# 15_Power_DCIN.net
KiCad netlist of a schematic drawn in Altium Designer
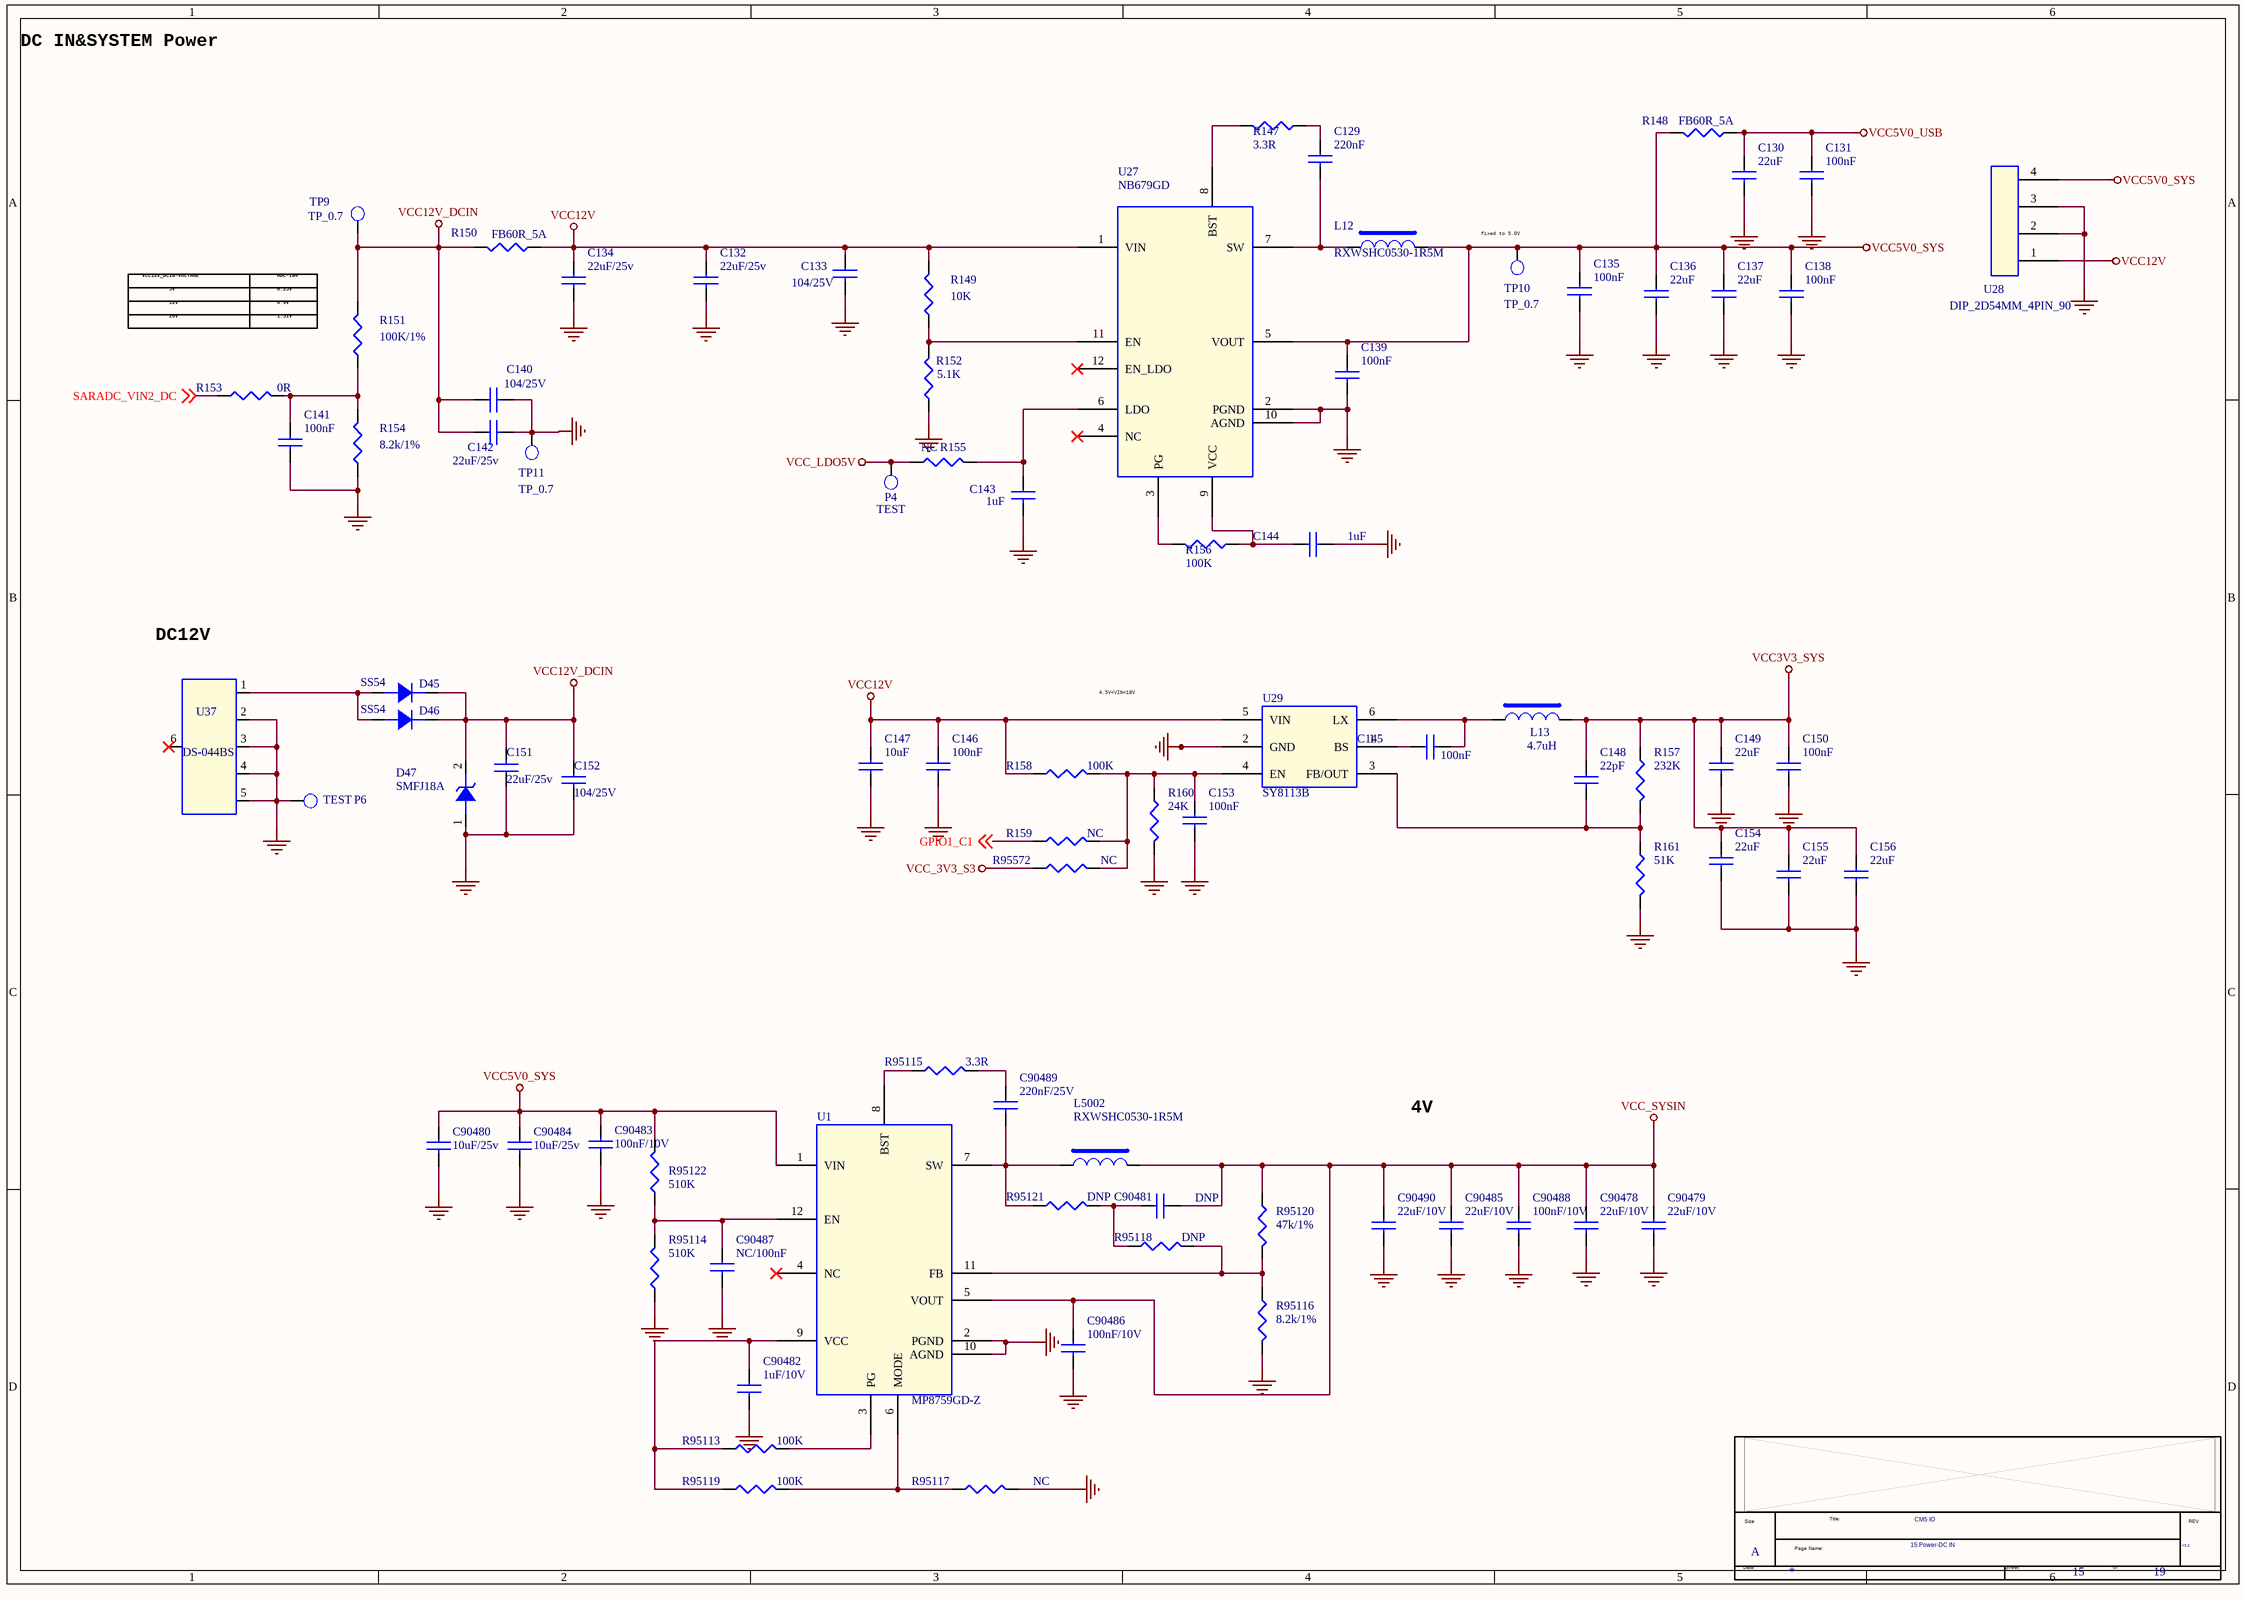
[diagram p0: 15_Power_DCIN.SchDoc]

(export (version "E")
  (design (tool "Eeschema 10.0.6"))
  (components
    (comp (ref "*")
      (value "radxa_1010")
      (fields
        (field (name "DOC") "15.Power-DC IN")
        (field (name "REVCODE") "V2.2")
        (field (name "TITLE") "CM5 IO")
        (field (name "PAGE SIZE") "A")
        (field (name "PAGE NUMBER") "15")
        (field (name "PAGE COUNT") "19")
      )
      (libsource (lib "*") (part "radxa_1010"))
    )
    (comp (ref "C129")
      (value "220nF")
      (footprint "C0402")
      (description "cap,220.00nF,+/-10%,25V,X5R,C0402")
      (fields
        (field (name "VOLTAGE") "25V")
        (field (name "MANUFACTURER") "TDK")
        (field (name "CREATED BY") "JJJ")
      )
      (libsource (lib "*") (part "CAP NP_0"))
    )
    (comp (ref "C130")
      (value "22uF")
      (footprint "C0603")
      (description "cap,22.00uF,+/-10%,10V,X5R,C0805")
      (fields
        (field (name "VOLTAGE") "10V")
        (field (name "TOLERANCE") "10%")
        (field (name "CREATED BY") "JJJ")
      )
      (libsource (lib "*") (part "CAP NP_0"))
    )
    (comp (ref "C131")
      (value "100nF")
      (footprint "C0402")
      (description "cap,100.00nF,+/-10%,16V,X5R,C0402")
      (fields
        (field (name "VOLTAGE") "16V")
        (field (name "MANUFACTURER") "TDK")
        (field (name "CREATED BY") "JJJ")
      )
      (libsource (lib "*") (part "CAP NP_0"))
    )
    (comp (ref "C132")
      (value "22uF/25v")
      (footprint "C0805")
      (description "cap,10.00uF,+/-10%,16V,X5R,C0805")
      (fields
        (field (name "VOLTAGE") "16V")
        (field (name "TOLERANCE") "10%")
        (field (name "CREATED BY") "JJJ")
      )
      (libsource (lib "*") (part "CAP NP_0"))
    )
    (comp (ref "C133")
      (value "104/25V")
      (footprint "C0402")
      (description "cap,1.00uF,+/-10%,16V,X5R,C0402")
      (fields
        (field (name "VOLTAGE") "25V")
        (field (name "MANUFACTURER") "TDK")
        (field (name "CREATED BY") "JJJ")
      )
      (libsource (lib "*") (part "CAP NP_0"))
    )
    (comp (ref "C134")
      (value "22uF/25v")
      (footprint "C0805")
      (description "cap,10.00uF,+/-10%,16V,X5R,C0805")
      (fields
        (field (name "VOLTAGE") "16V")
        (field (name "MANUFACTURER") "TDK")
        (field (name "CREATED BY") "JJJ")
      )
      (libsource (lib "*") (part "CAP NP_0"))
    )
    (comp (ref "C135")
      (value "100nF")
      (footprint "C0402")
      (description "cap,100.00nF,+/-10%,16V,X5R,C0402")
      (fields
        (field (name "VOLTAGE") "16V")
        (field (name "MANUFACTURER") "TDK")
        (field (name "CREATED BY") "JJJ")
      )
      (libsource (lib "*") (part "CAP NP_0"))
    )
    (comp (ref "C136")
      (value "22uF")
      (footprint "C0603")
      (description "cap,22.00uF,+/-10%,10V,X5R,C0805")
      (fields
        (field (name "VOLTAGE") "10V")
        (field (name "TOLERANCE") "10%")
        (field (name "CREATED BY") "JJJ")
      )
      (libsource (lib "*") (part "CAP NP_0"))
    )
    (comp (ref "C137")
      (value "22uF")
      (footprint "C0603")
      (description "cap,22.00uF,+/-10%,10V,X5R,C0805")
      (fields
        (field (name "VOLTAGE") "10V")
        (field (name "TOLERANCE") "10%")
        (field (name "CREATED BY") "JJJ")
      )
      (libsource (lib "*") (part "CAP NP_0"))
    )
    (comp (ref "C138")
      (value "100nF")
      (footprint "C0402")
      (description "cap,100.00nF,+/-10%,16V,X5R,C0402")
      (fields
        (field (name "VOLTAGE") "16V")
        (field (name "MANUFACTURER") "TDK")
        (field (name "CREATED BY") "JJJ")
      )
      (libsource (lib "*") (part "CAP NP_0"))
    )
    (comp (ref "C139")
      (value "100nF")
      (footprint "C0402")
      (description "cap,100.00nF,+/-10%,16V,X5R,C0402")
      (fields
        (field (name "VOLTAGE") "16V")
        (field (name "MANUFACTURER") "TDK")
        (field (name "CREATED BY") "JJJ")
      )
      (libsource (lib "*") (part "CAP NP_0"))
    )
    (comp (ref "C140")
      (value "104/25V")
      (footprint "C0402")
      (description "cap,1.00uF,+/-10%,16V,X5R,C0402")
      (fields
        (field (name "VOLTAGE") "25V")
        (field (name "MANUFACTURER") "TDK")
        (field (name "CREATED BY") "JJJ")
      )
      (libsource (lib "*") (part "CAP NP_0"))
    )
    (comp (ref "C141")
      (value "100nF")
      (footprint "C0402")
      (description "cap,100.00nF,+/-10%,16V,X5R,C0402")
      (fields
        (field (name "VOLTAGE") "16V")
        (field (name "TOLERANCE") "10%")
        (field (name "CREATED BY") "JJJ")
      )
      (libsource (lib "*") (part "CAP NP_0"))
    )
    (comp (ref "C142")
      (value "22uF/25v")
      (footprint "C0805")
      (description "cap,10.00uF,+/-10%,16V,X5R,C0805")
      (fields
        (field (name "VOLTAGE") "16V")
        (field (name "TOLERANCE") "10%")
        (field (name "CREATED BY") "JJJ")
      )
      (libsource (lib "*") (part "CAP NP_0"))
    )
    (comp (ref "C143")
      (value "1uF")
      (footprint "C0402")
      (description "cap,1.00uF,+/-10%,16V,X5R,C0402")
      (fields
        (field (name "VOLTAGE") "16V")
        (field (name "TOLERANCE") "10%")
        (field (name "CREATED BY") "JJJ")
      )
      (libsource (lib "*") (part "CAP NP_0"))
    )
    (comp (ref "C144")
      (value "1uF")
      (footprint "C0402")
      (description "cap,1.00uF,+/-10%,16V,X5R,C0402")
      (fields
        (field (name "VOLTAGE") "16V")
        (field (name "MANUFACTURER") "TDK")
        (field (name "CREATED BY") "JJJ")
      )
      (libsource (lib "*") (part "CAP NP_0"))
    )
    (comp (ref "C145")
      (value "100nF")
      (footprint "C0402")
      (description "cap,100.00nF,+/-10%,25V,X5R,C0402")
      (fields
        (field (name "VOLTAGE") "25V")
        (field (name "TOLERANCE") "10%")
        (field (name "CREATED BY") "JJJ")
      )
      (libsource (lib "*") (part "CAP NP_0"))
    )
    (comp (ref "C146")
      (value "100nF")
      (footprint "C0402")
      (description "cap,100.00nF,+/-10%,25V,X5R,C0402")
      (fields
        (field (name "VOLTAGE") "25V")
        (field (name "TOLERANCE") "10%")
        (field (name "CREATED BY") "JJJ")
      )
      (libsource (lib "*") (part "CAP NP_0"))
    )
    (comp (ref "C147")
      (value "10uF")
      (footprint "C1206")
      (description "cap,10.00uF,+/-10%,25V,X5R,C1206")
      (fields
        (field (name "VOLTAGE") "25V")
        (field (name "TOLERANCE") "10%")
        (field (name "CREATED BY") "JJJ")
      )
      (libsource (lib "*") (part "CAP NP_0"))
    )
    (comp (ref "C148")
      (value "22pF")
      (footprint "C0402")
      (description "cap,22.00pF,+/-5%,50V,C0G,C0402")
      (fields
        (field (name "VOLTAGE") "50V")
        (field (name "MANUFACTURER") "TDK")
        (field (name "CREATED BY") "JJJ")
      )
      (libsource (lib "*") (part "CAP NP_0"))
    )
    (comp (ref "C149")
      (value "22uF")
      (footprint "C0805")
      (description "cap,22.00uF,+/-10%,10V,X5R,C0805")
      (fields
        (field (name "VOLTAGE") "10V")
        (field (name "TOLERANCE") "10%")
        (field (name "CREATED BY") "JJJ")
      )
      (libsource (lib "*") (part "CAP NP_0"))
    )
    (comp (ref "C150")
      (value "100nF")
      (footprint "C0402")
      (description "cap,100.00nF,+/-10%,10V,X5R,C0402")
      (fields
        (field (name "VOLTAGE") "10V")
        (field (name "TOLERANCE") "10%")
        (field (name "CREATED BY") "JJJ")
      )
      (libsource (lib "*") (part "CAP NP_0"))
    )
    (comp (ref "C151") (value "22uF/25v") (footprint "C0805") (libsource (lib "*") (part "CAP NP_4")))
    (comp (ref "C152")
      (value "104/25V")
      (footprint "C0402")
      (description "CAP,MLCC,1nF,+/-10%,X5R,6.3V,SMD0402")
      (libsource (lib "*") (part "CAP NP"))
    )
    (comp (ref "C153")
      (value "100nF")
      (footprint "C0402")
      (description "cap,100.00nF,+/-10%,10V,X5R,C0402")
      (fields
        (field (name "VOLTAGE") "10V")
        (field (name "MANUFACTURER") "TDK")
        (field (name "CREATED BY") "JJJ")
      )
      (libsource (lib "*") (part "CAP NP_0"))
    )
    (comp (ref "C154")
      (value "22uF")
      (footprint "C0805")
      (description "cap,22.00uF,+/-10%,10V,X5R,C0805")
      (fields
        (field (name "VOLTAGE") "10V")
        (field (name "MANUFACTURER") "TDK")
        (field (name "CREATED BY") "JJJ")
      )
      (libsource (lib "*") (part "CAP NP_0"))
    )
    (comp (ref "C155")
      (value "22uF")
      (footprint "C0805")
      (description "cap,22.00uF,+/-10%,10V,X5R,C0805")
      (fields
        (field (name "VOLTAGE") "10V")
        (field (name "TOLERANCE") "10%")
        (field (name "CREATED BY") "JJJ")
      )
      (libsource (lib "*") (part "CAP NP_0"))
    )
    (comp (ref "C156")
      (value "22uF")
      (footprint "C0805")
      (description "cap,22.00uF,+/-10%,10V,X5R,C0805")
      (fields
        (field (name "VOLTAGE") "10V")
        (field (name "MANUFACTURER") "TDK")
        (field (name "CREATED BY") "JJJ")
      )
      (libsource (lib "*") (part "CAP NP_0"))
    )
    (comp (ref "C90478")
      (value "22uF/10V")
      (footprint "C0805")
      (description "cap,22.00uF,+/-10%,10V,X5R,C0805")
      (fields
        (field (name "VOLTAGE") "10V")
        (field (name "TOLERANCE") "10%")
        (field (name "CREATED BY") "JJJ")
      )
      (libsource (lib "*") (part "CAP NP_0_Dup2"))
    )
    (comp (ref "C90479")
      (value "22uF/10V")
      (footprint "C0805")
      (description "cap,22.00uF,+/-10%,10V,X5R,C0805")
      (fields
        (field (name "VOLTAGE") "10V")
        (field (name "TOLERANCE") "10%")
        (field (name "CREATED BY") "JJJ")
      )
      (libsource (lib "*") (part "CAP NP_0_Dup2"))
    )
    (comp (ref "C90480")
      (value "10uF/25v")
      (footprint "C1206")
      (description "cap,10.00uF,+/-10%,25V,X5R,C1206")
      (fields
        (field (name "VOLTAGE") "25V")
        (field (name "TOLERANCE") "10%")
        (field (name "CREATED BY") "JJJ")
      )
      (libsource (lib "*") (part "CAP NP_0_Dup2"))
    )
    (comp (ref "C90481")
      (value "DNP")
      (footprint "C0201")
      (description "Did Not Place.")
      (fields (field (name "CREATED BY") "JJJ"))
      (libsource (lib "*") (part "CAP NP_0_Dup2"))
    )
    (comp (ref "C90482")
      (value "1uF/10V")
      (footprint "C0201")
      (description "cap,1.00uF,+/-10%,10V,X5R,C0402")
      (fields
        (field (name "VOLTAGE") "10V")
        (field (name "MANUFACTURER") "TDK")
        (field (name "CREATED BY") "JJJ")
      )
      (libsource (lib "*") (part "CAP NP_0_Dup2"))
    )
    (comp (ref "C90483")
      (value "100nF/10V")
      (footprint "C0402")
      (description "cap,100.00nF,+/-10%,50V,X5R,C0603")
      (fields
        (field (name "VOLTAGE") "50V")
        (field (name "MANUFACTURER") "TDK")
        (field (name "CREATED BY") "JJJ")
      )
      (libsource (lib "*") (part "CAP NP_0_Dup2"))
    )
    (comp (ref "C90484")
      (value "10uF/25v")
      (footprint "C1206")
      (description "cap,10.00uF,+/-10%,25V,X5R,C1206")
      (fields
        (field (name "VOLTAGE") "25V")
        (field (name "MANUFACTURER") "TDK")
        (field (name "CREATED BY") "JJJ")
      )
      (libsource (lib "*") (part "CAP NP_0_Dup2"))
    )
    (comp (ref "C90485")
      (value "22uF/10V")
      (footprint "C0805")
      (description "cap,22.00uF,+/-10%,10V,X5R,C0805")
      (fields
        (field (name "VOLTAGE") "10V")
        (field (name "MANUFACTURER") "TDK")
        (field (name "CREATED BY") "JJJ")
      )
      (libsource (lib "*") (part "CAP NP_0_Dup2"))
    )
    (comp (ref "C90486")
      (value "100nF/10V")
      (footprint "C0201")
      (description "cap,100.00nF,+/-10%,10V,X5R,C0402")
      (fields
        (field (name "VOLTAGE") "10V")
        (field (name "TOLERANCE") "10%")
        (field (name "CREATED BY") "JJJ")
      )
      (libsource (lib "*") (part "CAP NP_0_Dup2"))
    )
    (comp (ref "C90487")
      (value "NC/100nF")
      (footprint "C0201")
      (description "cap,100.00nF,+/-10%,25V,X5R,C0402")
      (fields
        (field (name "VOLTAGE") "25V")
        (field (name "TOLERANCE") "10%")
        (field (name "CREATED BY") "JJJ")
      )
      (libsource (lib "*") (part "CAP NP_0_Dup2"))
    )
    (comp (ref "C90488")
      (value "100nF/10V")
      (footprint "C0402")
      (description "cap,100.00nF,+/-10%,10V,X5R,C0402")
      (fields
        (field (name "VOLTAGE") "10V")
        (field (name "MANUFACTURER") "TDK")
        (field (name "CREATED BY") "JJJ")
      )
      (libsource (lib "*") (part "CAP NP_0_Dup2"))
    )
    (comp (ref "C90489")
      (value "220nF/25V")
      (footprint "C0402")
      (description "cap,220.00nF,+/-10%,25V,X5R,C0402")
      (fields
        (field (name "VOLTAGE") "25V")
        (field (name "TOLERANCE") "10%")
        (field (name "CREATED BY") "JJJ")
      )
      (libsource (lib "*") (part "CAP NP_0_Dup2"))
    )
    (comp (ref "C90490")
      (value "22uF/10V")
      (footprint "C0805")
      (description "cap,22.00uF,+/-10%,10V,X5R,C0805")
      (fields
        (field (name "VOLTAGE") "10V")
        (field (name "TOLERANCE") "10%")
        (field (name "CREATED BY") "JJJ")
      )
      (libsource (lib "*") (part "CAP NP_0_Dup2"))
    )
    (comp (ref "D45")
      (value "SS54")
      (footprint "DO_214AC")
      (description "Schottky Barrier，SS32 DO214AC")
      (fields (field (name "MANUFACTURER") "星海") (field (name "CREATED BY") "JJJ"))
      (libsource (lib "*") (part "DIODE"))
    )
    (comp (ref "D46")
      (value "SS54")
      (footprint "DO_214AC")
      (description "Schottky Barrier，SS32 DO214AC")
      (fields (field (name "MANUFACTURER") "星海") (field (name "CREATED BY") "JJJ"))
      (libsource (lib "*") (part "DIODE"))
    )
    (comp (ref "D47")
      (value "SMFJ18A")
      (footprint "SOD_123")
      (description "1-Line, Uni-directional, Transient Voltage Suppressor")
      (fields (field (name "MANUFACTURER") "WillSemi(韦尔半导体)") (field (name "CREATED BY") "JJJ"))
      (libsource (lib "*") (part "DIODE ZENER1"))
    )
    (comp (ref "L12")
      (value "RXWSHC0530-1R5M")
      (footprint "IND-5020")
      (libsource (lib "*") (part "INDUCTORS OF FERRITE"))
    )
    (comp (ref "L13")
      (value "4.7uH")
      (footprint "IND-5020")
      (description "Power Inductor,4.7uH,0.2,IND_606045")
      (fields
        (field (name "MANUFACTURER") "sunlord")
        (field (name "TOLERANCE") "20%")
        (field (name "CREATED BY") "YWQ")
      )
      (libsource (lib "*") (part "INDUCTORS OF FERRITE_Dup1"))
    )
    (comp (ref "L5002")
      (value "RXWSHC0530-1R5M")
      (footprint "IND-5020")
      (description "Power Inductor,1.5uH,MWSA0603S-1R5MT")
      (fields
        (field (name "MANUFACTURER") "Vishay")
        (field (name "TOLERANCE") "20%")
        (field (name "CREATED BY") "JJJ")
      )
      (libsource (lib "*") (part "INDUCTORS OF FERRITE_Dup1"))
    )
    (comp (ref "P4") (value "TEST") (footprint "TEST") (libsource (lib "*") (part "TESTPOINT1")))
    (comp (ref "P6") (value "TEST") (footprint "TEST") (libsource (lib "*") (part "TESTPOINT1")))
    (comp (ref "R147")
      (value "3.3R")
      (footprint "R0402")
      (description "通用厚膜电阻,3R3,+/-5%,R0402,1/16W.")
      (fields
        (field (name "TOLERANCE") "5%")
        (field (name "MANUFACTURER") "YAGEO")
        (field (name "CREATED BY") "YTL")
      )
      (libsource (lib "*") (part "RESISTOR_0_Dup3"))
    )
    (comp (ref "R148") (value "FB60R_5A") (footprint "R1206") (libsource (lib "*") (part "R_0")))
    (comp (ref "R149")
      (value "10K")
      (footprint "R0402")
      (description "通用厚膜电阻,10K,+/-5%,R0402,1/16W.")
      (fields
        (field (name "TOLERANCE") "5%")
        (field (name "MANUFACTURER") "YAGEO")
        (field (name "CREATED BY") "YTL")
      )
      (libsource (lib "*") (part "RESISTOR_0_Dup3"))
    )
    (comp (ref "R150") (value "FB60R_5A") (footprint "R1206") (libsource (lib "*") (part "R_0")))
    (comp (ref "R151")
      (value "100K/1%")
      (footprint "R0402")
      (description "通用厚膜电阻,10K,+/-5%,R0402,1/16W.")
      (fields
        (field (name "TOLERANCE") "5%")
        (field (name "MANUFACTURER") "YAGEO")
        (field (name "CREATED BY") "YTL")
      )
      (libsource (lib "*") (part "RESISTOR_2"))
    )
    (comp (ref "R152")
      (value "5.1K")
      (footprint "R0402")
      (description "通用厚膜电阻,10K,+/-5%,R0402,1/16W.")
      (fields
        (field (name "TOLERANCE") "5%")
        (field (name "MANUFACTURER") "YAGEO")
        (field (name "CREATED BY") "YTL")
      )
      (libsource (lib "*") (part "RESISTOR_0_Dup3"))
    )
    (comp (ref "R153")
      (value "0R")
      (footprint "R0402")
      (description "通用厚膜电阻,10K,+/-5%,R0402,1/16W.")
      (fields
        (field (name "TOLERANCE") "5%")
        (field (name "MANUFACTURER") "YAGEO")
        (field (name "CREATED BY") "YTL")
      )
      (libsource (lib "*") (part "RESISTOR_2"))
    )
    (comp (ref "R154")
      (value "8.2k/1%")
      (footprint "R0402")
      (description "通用厚膜电阻,10K,+/-5%,R0402,1/16W.")
      (fields
        (field (name "TOLERANCE") "5%")
        (field (name "MANUFACTURER") "YAGEO")
        (field (name "CREATED BY") "YTL")
      )
      (libsource (lib "*") (part "RESISTOR_2"))
    )
    (comp (ref "R155")
      (value "NC")
      (footprint "R0402")
      (description "通用厚膜电阻,10K,+/-5%,R0402,1/16W.")
      (fields
        (field (name "TOLERANCE") "5%")
        (field (name "MANUFACTURER") "YAGEO")
        (field (name "CREATED BY") "YTL")
      )
      (libsource (lib "*") (part "RESISTOR_2"))
    )
    (comp (ref "R156")
      (value "100K")
      (footprint "R0402")
      (description "通用厚膜电阻,100K,+/-5%,R0402,1/16W.")
      (fields
        (field (name "TOLERANCE") "5%")
        (field (name "MANUFACTURER") "YAGEO")
        (field (name "CREATED BY") "YTL")
      )
      (libsource (lib "*") (part "RESISTOR_0_Dup3"))
    )
    (comp (ref "R157")
      (value "232K")
      (footprint "R0402")
      (description "通用厚膜电阻,232K,+/-1%,R0402,1/16W.")
      (fields
        (field (name "TOLERANCE") "1%")
        (field (name "MANUFACTURER") "YAGEO")
        (field (name "CREATED BY") "YTL")
      )
      (libsource (lib "*") (part "RESISTOR_0_Dup3"))
    )
    (comp (ref "R158")
      (value "100K")
      (footprint "R0402")
      (description "通用厚膜电阻,100K,+/-5%,R0402,1/16W.")
      (fields
        (field (name "TOLERANCE") "5%")
        (field (name "MANUFACTURER") "YAGEO")
        (field (name "CREATED BY") "YTL")
      )
      (libsource (lib "*") (part "RESISTOR_0_Dup3"))
    )
    (comp (ref "R159")
      (value "NC")
      (footprint "R0402")
      (description "通用厚膜电阻,100K,+/-5%,R0402,1/16W.")
      (fields
        (field (name "TOLERANCE") "5%")
        (field (name "MANUFACTURER") "YAGEO")
        (field (name "CREATED BY") "YTL")
      )
      (libsource (lib "*") (part "RESISTOR_0_Dup3"))
    )
    (comp (ref "R160")
      (value "24K")
      (footprint "R0402")
      (description "通用厚膜电阻,24K,+/-5%,R0402,1/16W.")
      (fields
        (field (name "TOLERANCE") "5%")
        (field (name "MANUFACTURER") "YAGEO")
        (field (name "CREATED BY") "YTL")
      )
      (libsource (lib "*") (part "RESISTOR_0_Dup3"))
    )
    (comp (ref "R161")
      (value "51K")
      (footprint "R0402")
      (description "通用厚膜电阻,49K9,+/-1%,R0402,1/16W.")
      (fields
        (field (name "TOLERANCE") "1%")
        (field (name "MANUFACTURER") "YAGEO")
        (field (name "CREATED BY") "YTL")
      )
      (libsource (lib "*") (part "RESISTOR_0_Dup3"))
    )
    (comp (ref "R95113")
      (value "100K")
      (footprint "R0402")
      (description "通用厚膜电阻,100K,+/-5%,R0402,1/16W.")
      (fields
        (field (name "TOLERANCE") "5%")
        (field (name "MANUFACTURER") "YAGEO")
        (field (name "CREATED BY") "YTL")
      )
      (libsource (lib "*") (part "RESISTOR_1_Dup1"))
    )
    (comp (ref "R95114")
      (value "510K")
      (footprint "R0402")
      (description "通用厚膜电阻,100K,+/-5%,R0402,1/16W.")
      (fields
        (field (name "TOLERANCE") "5%")
        (field (name "MANUFACTURER") "YAGEO")
        (field (name "CREATED BY") "YTL")
      )
      (libsource (lib "*") (part "RESISTOR_1_Dup1"))
    )
    (comp (ref "R95115")
      (value "3.3R")
      (footprint "R0402")
      (description "通用厚膜电阻,3R3,+/-5%,R0402,1/16W.")
      (fields
        (field (name "TOLERANCE") "5%")
        (field (name "MANUFACTURER") "YAGEO")
        (field (name "CREATED BY") "YTL")
      )
      (libsource (lib "*") (part "RESISTOR_1_Dup1"))
    )
    (comp (ref "R95116")
      (value "8.2k/1%")
      (footprint "R0402")
      (description "通用厚膜电阻,7K5,+/-1%,R0402,1/16W.")
      (fields
        (field (name "TOLERANCE") "1%")
        (field (name "MANUFACTURER") "YAGEO")
        (field (name "CREATED BY") "YTL")
      )
      (libsource (lib "*") (part "RESISTOR_1_Dup1"))
    )
    (comp (ref "R95117")
      (value "NC")
      (footprint "R0402")
      (description "通用厚膜电阻,100K,+/-5%,R0402,1/16W.")
      (fields
        (field (name "TOLERANCE") "5%")
        (field (name "MANUFACTURER") "YAGEO")
        (field (name "CREATED BY") "YTL")
      )
      (libsource (lib "*") (part "RESISTOR_1_Dup1"))
    )
    (comp (ref "R95118")
      (value "DNP")
      (footprint "R0402")
      (description "Did Not Place.")
      (fields (field (name "CREATED BY") "JJJ"))
      (libsource (lib "*") (part "RESISTOR_1_Dup1"))
    )
    (comp (ref "R95119")
      (value "100K")
      (footprint "R0402")
      (description "通用厚膜电阻,100K,+/-5%,R0402,1/16W.")
      (fields
        (field (name "TOLERANCE") "5%")
        (field (name "MANUFACTURER") "YAGEO")
        (field (name "CREATED BY") "YTL")
      )
      (libsource (lib "*") (part "RESISTOR_1_Dup1"))
    )
    (comp (ref "R95120")
      (value "47k/1%")
      (footprint "R0402")
      (description "通用厚膜电阻,43K,+/-1%,R0402,1/16W.")
      (fields
        (field (name "TOLERANCE") "1%")
        (field (name "MANUFACTURER") "YAGEO")
        (field (name "CREATED BY") "YTL")
      )
      (libsource (lib "*") (part "RESISTOR_1_Dup1"))
    )
    (comp (ref "R95121")
      (value "DNP")
      (footprint "R0402")
      (description "Did Not Place.")
      (fields (field (name "CREATED BY") "JJJ"))
      (libsource (lib "*") (part "RESISTOR_1_Dup1"))
    )
    (comp (ref "R95122")
      (value "510K")
      (footprint "R0402")
      (description "通用厚膜电阻,510K,+/-5%,R0402,1/16W.")
      (fields
        (field (name "TOLERANCE") "5%")
        (field (name "MANUFACTURER") "YAGEO")
        (field (name "CREATED BY") "YTL")
      )
      (libsource (lib "*") (part "RESISTOR_1_Dup1"))
    )
    (comp (ref "R95572")
      (value "NC")
      (footprint "R0402")
      (description "通用厚膜电阻,100K,+/-5%,R0402,1/16W.")
      (fields
        (field (name "TOLERANCE") "5%")
        (field (name "MANUFACTURER") "YAGEO")
        (field (name "CREATED BY") "YTL")
      )
      (libsource (lib "*") (part "RESISTOR_0_Dup3"))
    )
    (comp (ref "TP9")
      (value "TP_0.7")
      (footprint "TEST")
      (description "Test Point 0.7mm")
      (fields (field (name "CREATED BY") "JJJ"))
      (libsource (lib "*") (part "TP"))
    )
    (comp (ref "TP10")
      (value "TP_0.7")
      (footprint "TEST")
      (description "Test Point 0.7mm")
      (fields (field (name "CREATED BY") "JJJ"))
      (libsource (lib "*") (part "TP"))
    )
    (comp (ref "TP11")
      (value "TP_0.7")
      (footprint "TEST")
      (description "Test Point 0.7mm")
      (fields (field (name "CREATED BY") "JJJ"))
      (libsource (lib "*") (part "TP"))
    )
    (comp (ref "U1")
      (value "MP8759GD-Z")
      (footprint "QFN12_2R00X3R00X1R00")
      (libsource (lib "*") (part "MP8759_6"))
    )
    (comp (ref "U27")
      (value "NB679GD")
      (footprint "QFN12_3R00X2R00X0R90")
      (description "26 V, Low Iq, High Current, Fixed 5 V-8 A Synchronous Buck Converter with 100 mA LDO;")
      (fields (field (name "MANUFACTURER") "MPS （美国芯源）") (field (name "CREATED BY") "JJJ"))
      (libsource (lib "*") (part "DCDC_NB679"))
    )
    (comp (ref "U28")
      (value "DIP_2D54MM_4PIN_90")
      (footprint "XIAO_4PIN_2D54")
      (libsource (lib "*") (part "CON3_2"))
    )
    (comp (ref "U29")
      (value "SY8113B")
      (footprint "SOT_23_6")
      (fields (field (name "MANUFACTURER") "Silergy（矽力杰）") (field (name "CREATED BY") "JJJ"))
      (libsource (lib "*") (part "DCDC_SY8113"))
    )
    (comp (ref "U37") (value "DS-044BS") (footprint "DC-044A") (libsource (lib "*") (part "CON3_0")))
  )
  (nets
    (net (code "1") (name "GND") (class "Default")
      (node (ref "C130") (pin "2") (pinfunction "2_2") (pintype "passive"))
      (node (ref "C131") (pin "2") (pinfunction "2_2") (pintype "passive"))
      (node (ref "C132") (pin "2") (pinfunction "2_2") (pintype "passive"))
      (node (ref "C133") (pin "2") (pinfunction "2_2") (pintype "passive"))
      (node (ref "C134") (pin "2") (pinfunction "2_2") (pintype "passive"))
      (node (ref "C135") (pin "2") (pinfunction "2_2") (pintype "passive"))
      (node (ref "C136") (pin "2") (pinfunction "2_2") (pintype "passive"))
      (node (ref "C137") (pin "2") (pinfunction "2_2") (pintype "passive"))
      (node (ref "C138") (pin "2") (pinfunction "2_2") (pintype "passive"))
      (node (ref "C139") (pin "2") (pinfunction "2_2") (pintype "passive"))
      (node (ref "C140") (pin "2") (pinfunction "2_2") (pintype "passive"))
      (node (ref "C141") (pin "2") (pinfunction "2_2") (pintype "passive"))
      (node (ref "C142") (pin "2") (pinfunction "2_2") (pintype "passive"))
      (node (ref "C143") (pin "2") (pinfunction "2_2") (pintype "passive"))
      (node (ref "C144") (pin "2") (pinfunction "2_2") (pintype "passive"))
      (node (ref "C146") (pin "2") (pinfunction "2_2") (pintype "passive"))
      (node (ref "C147") (pin "2") (pinfunction "2_2") (pintype "passive"))
      (node (ref "C149") (pin "2") (pinfunction "2_2") (pintype "passive"))
      (node (ref "C150") (pin "2") (pinfunction "2_2") (pintype "passive"))
      (node (ref "C151") (pin "1") (pinfunction "1_1") (pintype "passive"))
      (node (ref "C152") (pin "2") (pinfunction "2_2") (pintype "passive"))
      (node (ref "C153") (pin "2") (pinfunction "2_2") (pintype "passive"))
      (node (ref "C154") (pin "2") (pinfunction "2_2") (pintype "passive"))
      (node (ref "C155") (pin "2") (pinfunction "2_2") (pintype "passive"))
      (node (ref "C156") (pin "2") (pinfunction "2_2") (pintype "passive"))
      (node (ref "C90478") (pin "2") (pinfunction "2_2") (pintype "passive"))
      (node (ref "C90479") (pin "2") (pinfunction "2_2") (pintype "passive"))
      (node (ref "C90480") (pin "2") (pinfunction "2_2") (pintype "passive"))
      (node (ref "C90482") (pin "2") (pinfunction "2_2") (pintype "passive"))
      (node (ref "C90483") (pin "2") (pinfunction "2_2") (pintype "passive"))
      (node (ref "C90484") (pin "2") (pinfunction "2_2") (pintype "passive"))
      (node (ref "C90485") (pin "2") (pinfunction "2_2") (pintype "passive"))
      (node (ref "C90486") (pin "2") (pinfunction "2_2") (pintype "passive"))
      (node (ref "C90487") (pin "2") (pinfunction "2_2") (pintype "passive"))
      (node (ref "C90488") (pin "2") (pinfunction "2_2") (pintype "passive"))
      (node (ref "C90490") (pin "2") (pinfunction "2_2") (pintype "passive"))
      (node (ref "D47") (pin "1") (pinfunction "ANODE_1") (pintype "passive"))
      (node (ref "P6") (pin "1") (pinfunction "1_1") (pintype "passive"))
      (node (ref "R152") (pin "1") (pinfunction "1_1") (pintype "passive"))
      (node (ref "R154") (pin "1") (pinfunction "1_1") (pintype "passive"))
      (node (ref "R160") (pin "2") (pinfunction "2_2") (pintype "passive"))
      (node (ref "R161") (pin "2") (pinfunction "2_2") (pintype "passive"))
      (node (ref "R95114") (pin "1") (pinfunction "1_1") (pintype "passive"))
      (node (ref "R95116") (pin "2") (pinfunction "2_2") (pintype "passive"))
      (node (ref "R95117") (pin "2") (pinfunction "2_2") (pintype "passive"))
      (node (ref "TP11") (pin "1") (pinfunction "1_1") (pintype "passive"))
      (node (ref "U1") (pin "10") (pinfunction "AGND_10") (pintype "passive"))
      (node (ref "U1") (pin "2") (pinfunction "PGND_2") (pintype "passive"))
      (node (ref "U27") (pin "10") (pinfunction "AGND_10") (pintype "passive"))
      (node (ref "U27") (pin "2") (pinfunction "PGND_2") (pintype "passive"))
      (node (ref "U28") (pin "2") (pinfunction "2_2") (pintype "passive"))
      (node (ref "U28") (pin "3") (pinfunction "3_3") (pintype "passive"))
      (node (ref "U29") (pin "2") (pinfunction "GND_2") (pintype "passive"))
      (node (ref "U37") (pin "2") (pinfunction "2_2") (pintype "passive"))
      (node (ref "U37") (pin "3") (pinfunction "3_3") (pintype "passive"))
      (node (ref "U37") (pin "4") (pinfunction "4_4") (pintype "passive"))
      (node (ref "U37") (pin "5") (pinfunction "5_5") (pintype "passive"))
    )
    (net (code "2") (name "GPIO1_C1") (class "Default")
      (node (ref "R159") (pin "1") (pinfunction "1_1") (pintype "passive"))
    )
    (net (code "3") (name "Net-(C129-Pad1)") (class "Default")
      (node (ref "C129") (pin "1") (pinfunction "1_1") (pintype "passive"))
      (node (ref "R147") (pin "2") (pinfunction "2_2") (pintype "passive"))
    )
    (net (code "4") (name "Net-(C141-Pad1)") (class "Default")
      (node (ref "C141") (pin "1") (pinfunction "1_1") (pintype "passive"))
      (node (ref "R151") (pin "1") (pinfunction "1_1") (pintype "passive"))
      (node (ref "R153") (pin "2") (pinfunction "2_2") (pintype "passive"))
      (node (ref "R154") (pin "2") (pinfunction "2_2") (pintype "passive"))
    )
    (net (code "5") (name "Net-(C90481-Pad1)") (class "Default")
      (node (ref "C90481") (pin "1") (pinfunction "1_1") (pintype "passive"))
      (node (ref "R95118") (pin "1") (pinfunction "1_1") (pintype "passive"))
      (node (ref "R95121") (pin "2") (pinfunction "2_2") (pintype "passive"))
    )
    (net (code "6") (name "Net-(C90489-Pad1)") (class "Default")
      (node (ref "C90489") (pin "1") (pinfunction "1_1") (pintype "passive"))
      (node (ref "R95115") (pin "2") (pinfunction "2_2") (pintype "passive"))
    )
    (net (code "7") (name "Net-(D45-A)") (class "Default")
      (node (ref "D45") (pin "1") (pinfunction "A_1") (pintype "passive"))
      (node (ref "D46") (pin "1") (pinfunction "A_1") (pintype "passive"))
      (node (ref "U37") (pin "1") (pinfunction "1_1") (pintype "passive"))
    )
    (net (code "8") (name "Net-(U1-BST)") (class "Default")
      (node (ref "R95115") (pin "1") (pinfunction "1_1") (pintype "passive"))
      (node (ref "U1") (pin "8") (pinfunction "BST_8") (pintype "passive"))
    )
    (net (code "9") (name "Net-(U1-EN)") (class "Default")
      (node (ref "C90487") (pin "1") (pinfunction "1_1") (pintype "passive"))
      (node (ref "R95114") (pin "2") (pinfunction "2_2") (pintype "passive"))
      (node (ref "R95122") (pin "1") (pinfunction "1_1") (pintype "passive"))
      (node (ref "U1") (pin "12") (pinfunction "EN_12") (pintype "passive"))
    )
    (net (code "10") (name "Net-(U1-FB)") (class "Default")
      (node (ref "R95116") (pin "1") (pinfunction "1_1") (pintype "passive"))
      (node (ref "R95118") (pin "2") (pinfunction "2_2") (pintype "passive"))
      (node (ref "R95120") (pin "2") (pinfunction "2_2") (pintype "passive"))
      (node (ref "U1") (pin "11") (pinfunction "FB_11") (pintype "passive"))
    )
    (net (code "11") (name "Net-(U1-MODE)") (class "Default")
      (node (ref "R95117") (pin "1") (pinfunction "1_1") (pintype "passive"))
      (node (ref "R95119") (pin "2") (pinfunction "2_2") (pintype "passive"))
      (node (ref "U1") (pin "6") (pinfunction "MODE_6") (pintype "passive"))
    )
    (net (code "12") (name "Net-(U1-PG)") (class "Default")
      (node (ref "R95113") (pin "2") (pinfunction "2_2") (pintype "passive"))
      (node (ref "U1") (pin "3") (pinfunction "PG_3") (pintype "passive"))
    )
    (net (code "13") (name "Net-(U1-SW)") (class "Default")
      (node (ref "C90489") (pin "2") (pinfunction "2_2") (pintype "passive"))
      (node (ref "L5002") (pin "1") (pinfunction "1_1") (pintype "passive"))
      (node (ref "R95121") (pin "1") (pinfunction "1_1") (pintype "passive"))
      (node (ref "U1") (pin "7") (pinfunction "SW_7") (pintype "passive"))
    )
    (net (code "14") (name "Net-(U1-VCC)") (class "Default")
      (node (ref "C90482") (pin "1") (pinfunction "1_1") (pintype "passive"))
      (node (ref "R95113") (pin "1") (pinfunction "1_1") (pintype "passive"))
      (node (ref "R95119") (pin "1") (pinfunction "1_1") (pintype "passive"))
      (node (ref "U1") (pin "9") (pinfunction "VCC_9") (pintype "passive"))
    )
    (net (code "15") (name "Net-(U27-BST)") (class "Default")
      (node (ref "R147") (pin "1") (pinfunction "1_1") (pintype "passive"))
      (node (ref "U27") (pin "8") (pinfunction "BST_8") (pintype "passive"))
    )
    (net (code "16") (name "Net-(U27-EN)") (class "Default")
      (node (ref "R149") (pin "1") (pinfunction "1_1") (pintype "passive"))
      (node (ref "R152") (pin "2") (pinfunction "2_2") (pintype "passive"))
      (node (ref "U27") (pin "11") (pinfunction "EN_11") (pintype "passive"))
    )
    (net (code "17") (name "Net-(U27-LDO)") (class "Default")
      (node (ref "C143") (pin "1") (pinfunction "1_1") (pintype "passive"))
      (node (ref "R155") (pin "2") (pinfunction "2_2") (pintype "passive"))
      (node (ref "U27") (pin "6") (pinfunction "LDO_6") (pintype "passive"))
    )
    (net (code "18") (name "Net-(U27-PG)") (class "Default")
      (node (ref "R156") (pin "1") (pinfunction "1_1") (pintype "passive"))
      (node (ref "U27") (pin "3") (pinfunction "PG_3") (pintype "passive"))
    )
    (net (code "19") (name "Net-(U27-SW)") (class "Default")
      (node (ref "C129") (pin "2") (pinfunction "2_2") (pintype "passive"))
      (node (ref "L12") (pin "1") (pinfunction "1_1") (pintype "passive"))
      (node (ref "U27") (pin "7") (pinfunction "SW_7") (pintype "passive"))
    )
    (net (code "20") (name "Net-(U27-VCC)") (class "Default")
      (node (ref "C144") (pin "1") (pinfunction "1_1") (pintype "passive"))
      (node (ref "R156") (pin "2") (pinfunction "2_2") (pintype "passive"))
      (node (ref "U27") (pin "9") (pinfunction "VCC_9") (pintype "passive"))
    )
    (net (code "21") (name "Net-(U29-BS)") (class "Default")
      (node (ref "C145") (pin "1") (pinfunction "1_1") (pintype "passive"))
      (node (ref "U29") (pin "1") (pinfunction "BS_1") (pintype "passive"))
    )
    (net (code "22") (name "Net-(U29-EN)") (class "Default")
      (node (ref "C153") (pin "1") (pinfunction "1_1") (pintype "passive"))
      (node (ref "R158") (pin "2") (pinfunction "2_2") (pintype "passive"))
      (node (ref "R159") (pin "2") (pinfunction "2_2") (pintype "passive"))
      (node (ref "R160") (pin "1") (pinfunction "1_1") (pintype "passive"))
      (node (ref "R95572") (pin "2") (pinfunction "2_2") (pintype "passive"))
      (node (ref "U29") (pin "4") (pinfunction "EN_4") (pintype "passive"))
    )
    (net (code "23") (name "Net-(U29-FB{slash}OUT)") (class "Default")
      (node (ref "C148") (pin "2") (pinfunction "2_2") (pintype "passive"))
      (node (ref "R157") (pin "2") (pinfunction "2_2") (pintype "passive"))
      (node (ref "R161") (pin "1") (pinfunction "1_1") (pintype "passive"))
      (node (ref "U29") (pin "3") (pinfunction "FB/OUT_3") (pintype "passive"))
    )
    (net (code "24") (name "Net-(U29-LX)") (class "Default")
      (node (ref "C145") (pin "2") (pinfunction "2_2") (pintype "passive"))
      (node (ref "L13") (pin "1") (pinfunction "1_1") (pintype "passive"))
      (node (ref "U29") (pin "6") (pinfunction "LX_6") (pintype "passive"))
    )
    (net (code "25") (name "SARADC_VIN2_DC") (class "Default")
      (node (ref "R153") (pin "1") (pinfunction "1_1") (pintype "passive"))
    )
    (net (code "26") (name "VCC3V3_SYS") (class "Default")
      (node (ref "C148") (pin "1") (pinfunction "1_1") (pintype "passive"))
      (node (ref "C149") (pin "1") (pinfunction "1_1") (pintype "passive"))
      (node (ref "C150") (pin "1") (pinfunction "1_1") (pintype "passive"))
      (node (ref "C154") (pin "1") (pinfunction "1_1") (pintype "passive"))
      (node (ref "C155") (pin "1") (pinfunction "1_1") (pintype "passive"))
      (node (ref "C156") (pin "1") (pinfunction "1_1") (pintype "passive"))
      (node (ref "L13") (pin "2") (pinfunction "2_2") (pintype "passive"))
      (node (ref "R157") (pin "1") (pinfunction "1_1") (pintype "passive"))
    )
    (net (code "27") (name "VCC5V0_SYS") (class "Default")
      (node (ref "C135") (pin "1") (pinfunction "1_1") (pintype "passive"))
      (node (ref "C136") (pin "1") (pinfunction "1_1") (pintype "passive"))
      (node (ref "C137") (pin "1") (pinfunction "1_1") (pintype "passive"))
      (node (ref "C138") (pin "1") (pinfunction "1_1") (pintype "passive"))
      (node (ref "C139") (pin "1") (pinfunction "1_1") (pintype "passive"))
      (node (ref "C90480") (pin "1") (pinfunction "1_1") (pintype "passive"))
      (node (ref "C90483") (pin "1") (pinfunction "1_1") (pintype "passive"))
      (node (ref "C90484") (pin "1") (pinfunction "1_1") (pintype "passive"))
      (node (ref "L12") (pin "2") (pinfunction "2_2") (pintype "passive"))
      (node (ref "R148") (pin "2") (pinfunction "2_2") (pintype "passive"))
      (node (ref "R95122") (pin "2") (pinfunction "2_2") (pintype "passive"))
      (node (ref "TP10") (pin "1") (pinfunction "1_1") (pintype "passive"))
      (node (ref "U1") (pin "1") (pinfunction "VIN_1") (pintype "passive"))
      (node (ref "U27") (pin "5") (pinfunction "VOUT_5") (pintype "passive"))
      (node (ref "U28") (pin "4") (pinfunction "4_4") (pintype "passive"))
    )
    (net (code "28") (name "VCC5V0_USB") (class "Default")
      (node (ref "C130") (pin "1") (pinfunction "1_1") (pintype "passive"))
      (node (ref "C131") (pin "1") (pinfunction "1_1") (pintype "passive"))
      (node (ref "R148") (pin "1") (pinfunction "1_1") (pintype "passive"))
    )
    (net (code "29") (name "VCC12V") (class "Default")
      (node (ref "C132") (pin "1") (pinfunction "1_1") (pintype "passive"))
      (node (ref "C133") (pin "1") (pinfunction "1_1") (pintype "passive"))
      (node (ref "C134") (pin "1") (pinfunction "1_1") (pintype "passive"))
      (node (ref "C146") (pin "1") (pinfunction "1_1") (pintype "passive"))
      (node (ref "C147") (pin "1") (pinfunction "1_1") (pintype "passive"))
      (node (ref "R149") (pin "2") (pinfunction "2_2") (pintype "passive"))
      (node (ref "R150") (pin "1") (pinfunction "1_1") (pintype "passive"))
      (node (ref "R158") (pin "1") (pinfunction "1_1") (pintype "passive"))
      (node (ref "U27") (pin "1") (pinfunction "VIN_1") (pintype "passive"))
      (node (ref "U28") (pin "1") (pinfunction "1_1") (pintype "passive"))
      (node (ref "U29") (pin "5") (pinfunction "VIN_5") (pintype "passive"))
    )
    (net (code "30") (name "VCC12V_DCIN") (class "Default")
      (node (ref "C140") (pin "1") (pinfunction "1_1") (pintype "passive"))
      (node (ref "C142") (pin "1") (pinfunction "1_1") (pintype "passive"))
      (node (ref "C151") (pin "2") (pinfunction "2_2") (pintype "passive"))
      (node (ref "C152") (pin "1") (pinfunction "1_1") (pintype "passive"))
      (node (ref "D45") (pin "2") (pinfunction "K_2") (pintype "passive"))
      (node (ref "D46") (pin "2") (pinfunction "K_2") (pintype "passive"))
      (node (ref "D47") (pin "2") (pinfunction "CATHODE_2") (pintype "passive"))
      (node (ref "R150") (pin "2") (pinfunction "2_2") (pintype "passive"))
      (node (ref "R151") (pin "2") (pinfunction "2_2") (pintype "passive"))
      (node (ref "TP9") (pin "1") (pinfunction "1_1") (pintype "passive"))
    )
    (net (code "31") (name "VCC_3V3_S3") (class "Default")
      (node (ref "R95572") (pin "1") (pinfunction "1_1") (pintype "passive"))
    )
    (net (code "32") (name "VCC_LDO5V") (class "Default")
      (node (ref "P4") (pin "1") (pinfunction "1_1") (pintype "passive"))
      (node (ref "R155") (pin "1") (pinfunction "1_1") (pintype "passive"))
    )
    (net (code "33") (name "VCC_SYSIN") (class "Default")
      (node (ref "C90478") (pin "1") (pinfunction "1_1") (pintype "passive"))
      (node (ref "C90479") (pin "1") (pinfunction "1_1") (pintype "passive"))
      (node (ref "C90481") (pin "2") (pinfunction "2_2") (pintype "passive"))
      (node (ref "C90485") (pin "1") (pinfunction "1_1") (pintype "passive"))
      (node (ref "C90486") (pin "1") (pinfunction "1_1") (pintype "passive"))
      (node (ref "C90488") (pin "1") (pinfunction "1_1") (pintype "passive"))
      (node (ref "C90490") (pin "1") (pinfunction "1_1") (pintype "passive"))
      (node (ref "L5002") (pin "2") (pinfunction "2_2") (pintype "passive"))
      (node (ref "R95120") (pin "1") (pinfunction "1_1") (pintype "passive"))
      (node (ref "U1") (pin "5") (pinfunction "VOUT_5") (pintype "passive"))
    )
    (net (code "34") (name "unconnected-(U1-NC-Pad4)") (class "Default")
      (node (ref "U1") (pin "4") (pinfunction "NC_4") (pintype "passive+no_connect"))
    )
    (net (code "35") (name "unconnected-(U27-EN_LDO-Pad12)") (class "Default")
      (node (ref "U27") (pin "12") (pinfunction "EN_LDO_12") (pintype "passive+no_connect"))
    )
    (net (code "36") (name "unconnected-(U27-NC-Pad4)") (class "Default")
      (node (ref "U27") (pin "4") (pinfunction "NC_4") (pintype "passive+no_connect"))
    )
    (net (code "37") (name "unconnected-(U37-Pad6)") (class "Default")
      (node (ref "U37") (pin "6") (pinfunction "6_6") (pintype "passive+no_connect"))
    )
  )
)
